# SCH_URC-VPN-New-Project_2025-07-22_1.net
KiCad netlist of a schematic drawn in EasyEDA
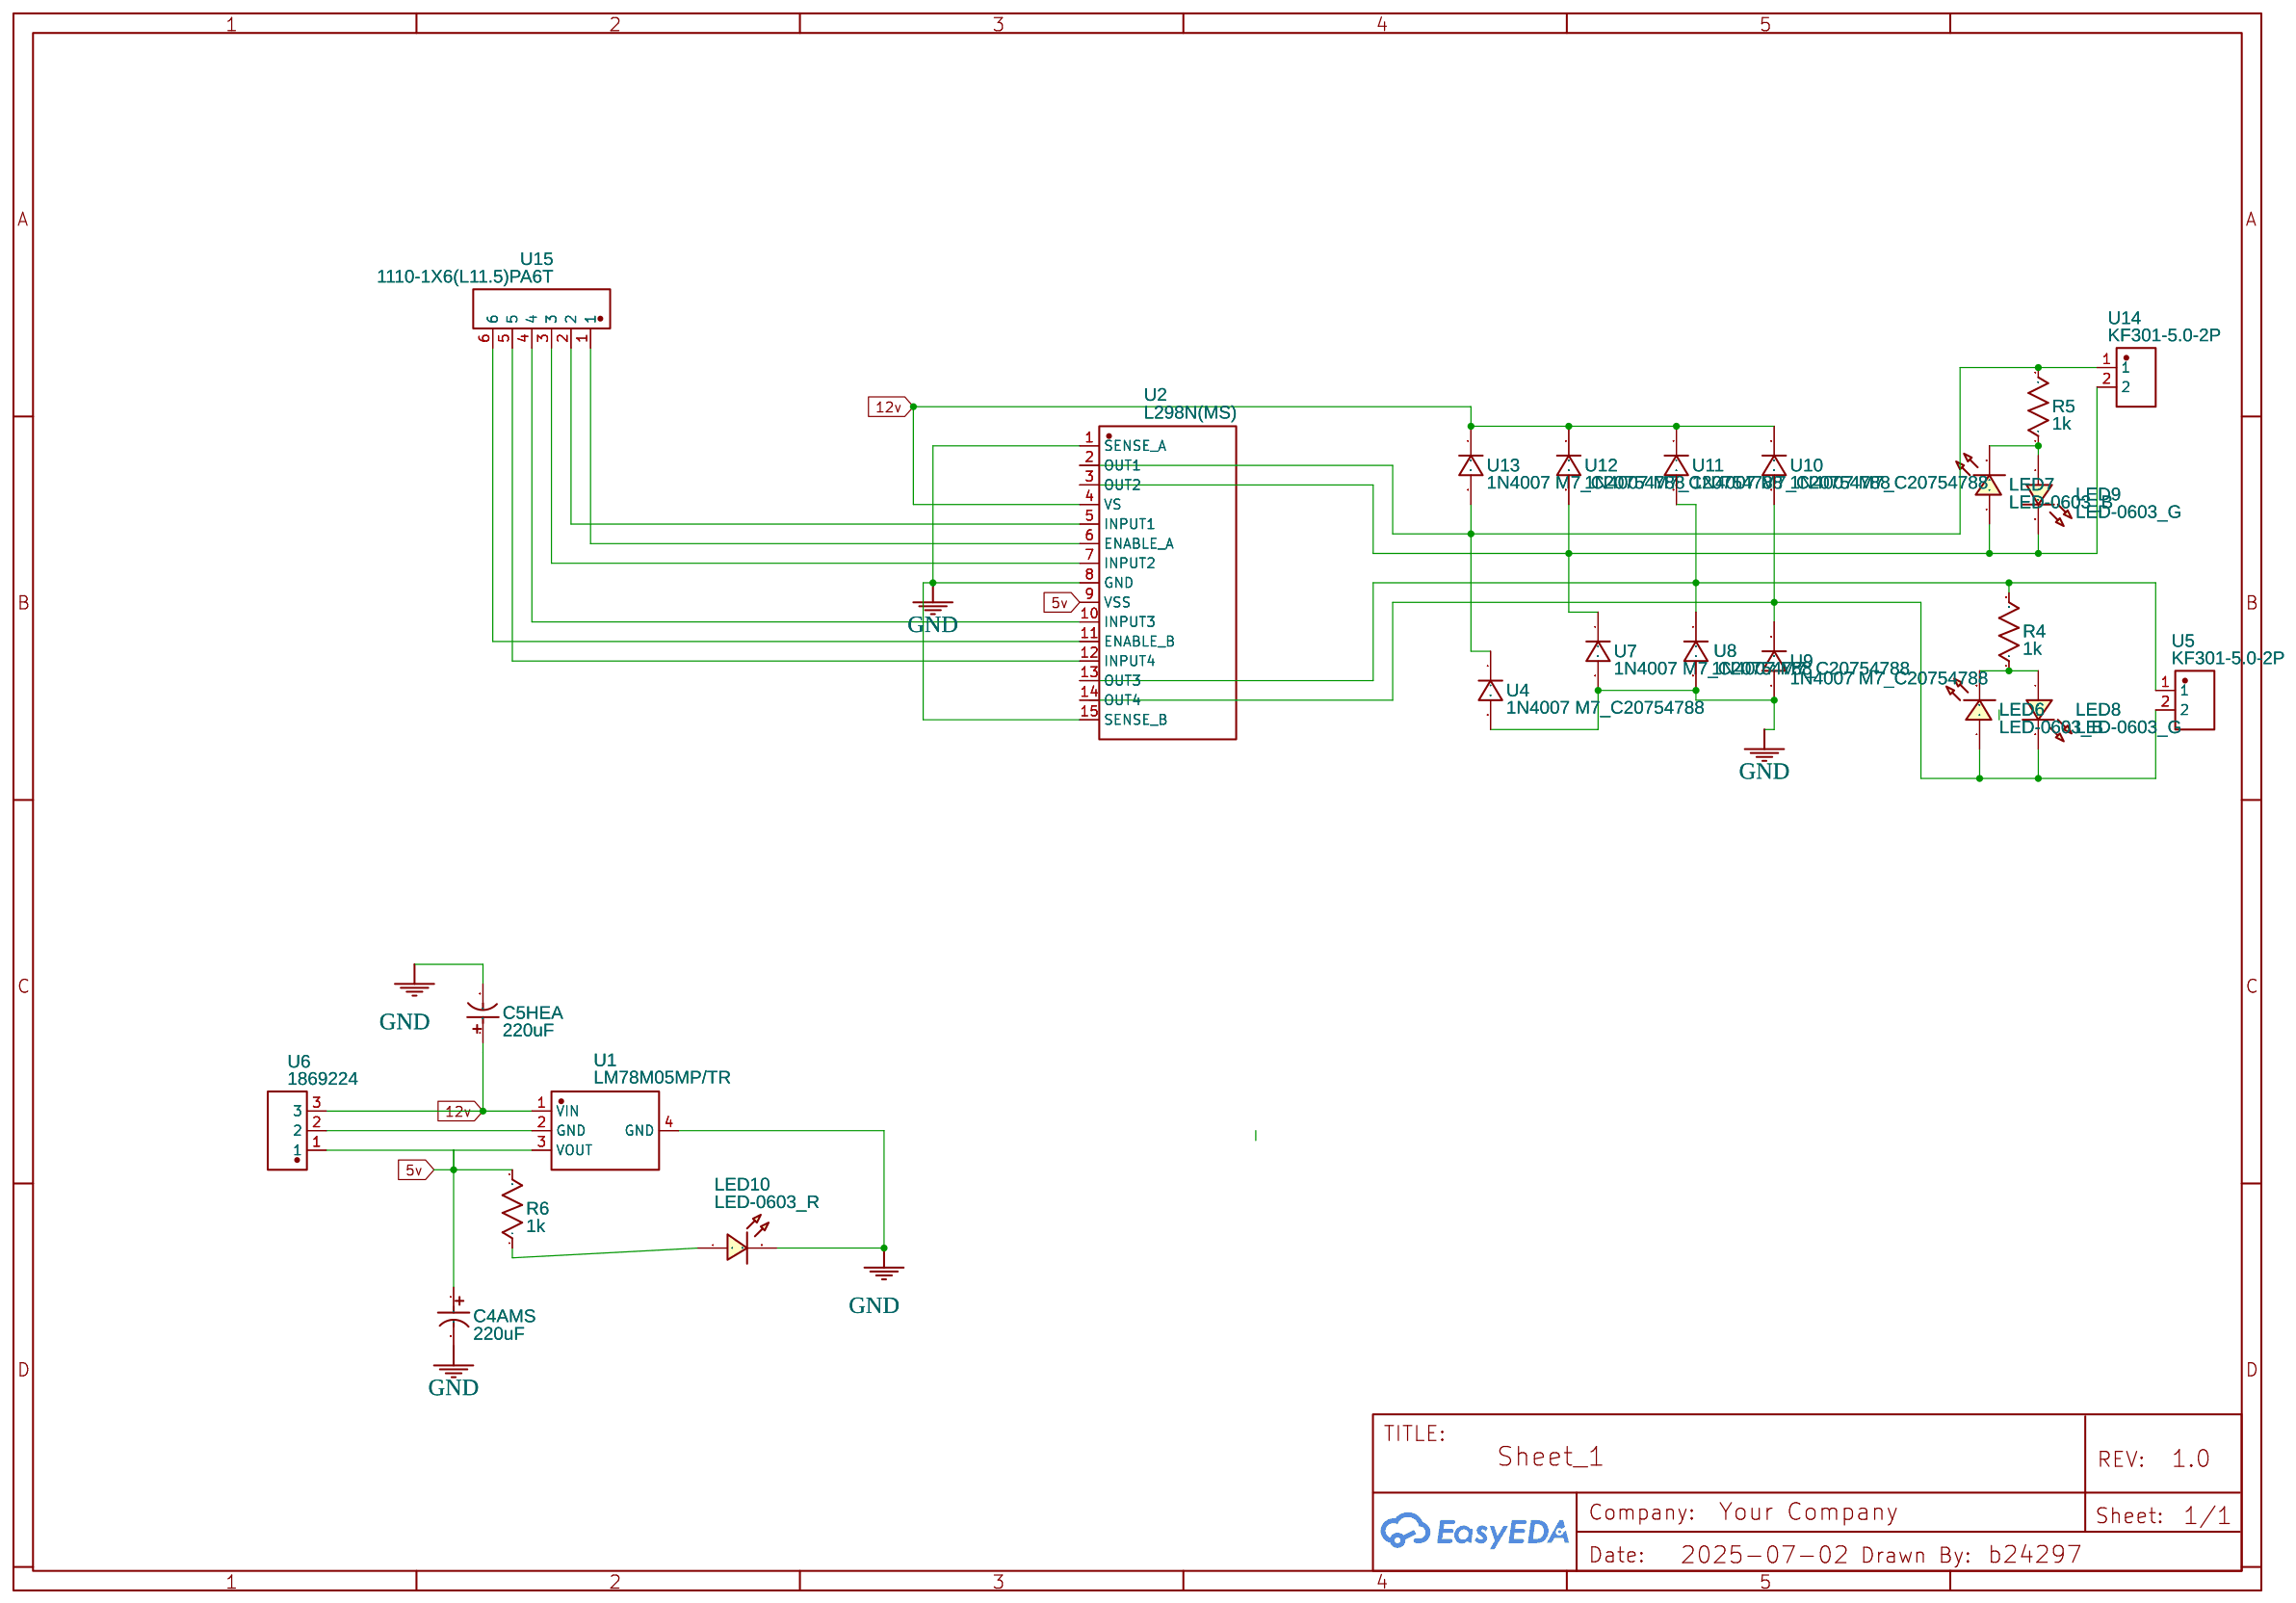
[diagram p0: schematic sheet]

(export (version "E")
  (design (tool "Eeschema 10.0.6"))
  (components
    (comp (ref "C4AMS")
      (value "220uF")
      (fields
        (field (name "Manufacturer Part") "KM227M035F12RR0VH2FP0")
        (field (name "Manufacturer") "CX(承兴)")
      )
      (libsource (lib "") (part "220uf/35V"))
    )
    (comp (ref "C5HEA")
      (value "220uF")
      (fields
        (field (name "Manufacturer Part") "KM227M035F12RR0VH2FP0")
        (field (name "Manufacturer") "CX(承兴)")
      )
      (libsource (lib "") (part "220uf/35V_1"))
    )
    (comp (ref "LED6")
      (value "LED-0603_B")
      (fields
        (field (name "Manufacturer Part") "19-217/BHC-ZL1M2RY/3T")
        (field (name "Manufacturer") "EVERLIGHT(台湾亿光)")
      )
      (libsource (lib "") (part "LED-0603_B"))
    )
    (comp (ref "LED7")
      (value "LED-0603_B")
      (fields
        (field (name "Manufacturer Part") "19-217/BHC-ZL1M2RY/3T")
        (field (name "Manufacturer") "EVERLIGHT(台湾亿光)")
      )
      (libsource (lib "") (part "LED-0603_B"))
    )
    (comp (ref "LED8")
      (value "LED-0603_G")
      (fields
        (field (name "Manufacturer Part") "19-217/GHC-YR1S2/3T")
        (field (name "Manufacturer") "EVERLIGHT(台湾亿光)")
      )
      (libsource (lib "") (part "LED-0603_G"))
    )
    (comp (ref "LED9")
      (value "LED-0603_G")
      (fields
        (field (name "Manufacturer Part") "19-217/GHC-YR1S2/3T")
        (field (name "Manufacturer") "EVERLIGHT(台湾亿光)")
      )
      (libsource (lib "") (part "LED-0603_G"))
    )
    (comp (ref "LED10")
      (value "LED-0603_R")
      (fields
        (field (name "Manufacturer Part") "19-217/R6C-AL1M2VY/3T")
        (field (name "Manufacturer") "EVERLIGHT(台湾亿光)")
      )
      (libsource (lib "") (part "LED-0603_R"))
    )
    (comp (ref "R4") (value "1k") (libsource (lib "") (part "R_0603_US")))
    (comp (ref "R5") (value "1k") (libsource (lib "") (part "R_0603_US")))
    (comp (ref "R6") (value "1k") (libsource (lib "") (part "R_0603_US")))
    (comp (ref "U1")
      (value "LM78M05MP/TR")
      (fields (field (name "Manufacturer") "HGSEMI(华冠)"))
      (libsource (lib "") (part "LM78M05MP/TR"))
    )
    (comp (ref "U2")
      (value "L298N(MS)")
      (fields (field (name "Manufacturer") "MSKSEMI(美森科)"))
      (libsource (lib "") (part "L298N(MS)"))
    )
    (comp (ref "U4")
      (value "1N4007 M7_C20754788")
      (fields (field (name "Manufacturer Part") "1N4007 M7") (field (name "Manufacturer") "JSMSEMI(杰盛微)"))
      (libsource (lib "") (part "1N4007 M7_C20754788"))
    )
    (comp (ref "U5")
      (value "KF301-5.0-2P")
      (fields (field (name "Manufacturer") "KEFA(科发)"))
      (libsource (lib "") (part "KF301-5.0-2P"))
    )
    (comp (ref "U6")
      (value "1869224")
      (fields (field (name "Manufacturer") "Phoenix Contact(菲尼克斯)"))
      (libsource (lib "") (part "1869224"))
    )
    (comp (ref "U7")
      (value "1N4007 M7_C20754788")
      (fields (field (name "Manufacturer Part") "1N4007 M7") (field (name "Manufacturer") "JSMSEMI(杰盛微)"))
      (libsource (lib "") (part "1N4007 M7_C20754788"))
    )
    (comp (ref "U8")
      (value "1N4007 M7_C20754788")
      (fields (field (name "Manufacturer Part") "1N4007 M7") (field (name "Manufacturer") "JSMSEMI(杰盛微)"))
      (libsource (lib "") (part "1N4007 M7_C20754788"))
    )
    (comp (ref "U9")
      (value "1N4007 M7_C20754788")
      (fields (field (name "Manufacturer Part") "1N4007 M7") (field (name "Manufacturer") "JSMSEMI(杰盛微)"))
      (libsource (lib "") (part "1N4007 M7_C20754788"))
    )
    (comp (ref "U10")
      (value "1N4007 M7_C20754788")
      (fields (field (name "Manufacturer Part") "1N4007 M7") (field (name "Manufacturer") "JSMSEMI(杰盛微)"))
      (libsource (lib "") (part "1N4007 M7_C20754788"))
    )
    (comp (ref "U11")
      (value "1N4007 M7_C20754788")
      (fields (field (name "Manufacturer Part") "1N4007 M7") (field (name "Manufacturer") "JSMSEMI(杰盛微)"))
      (libsource (lib "") (part "1N4007 M7_C20754788"))
    )
    (comp (ref "U12")
      (value "1N4007 M7_C20754788")
      (fields (field (name "Manufacturer Part") "1N4007 M7") (field (name "Manufacturer") "JSMSEMI(杰盛微)"))
      (libsource (lib "") (part "1N4007 M7_C20754788"))
    )
    (comp (ref "U13")
      (value "1N4007 M7_C20754788")
      (fields (field (name "Manufacturer Part") "1N4007 M7") (field (name "Manufacturer") "JSMSEMI(杰盛微)"))
      (libsource (lib "") (part "1N4007 M7_C20754788"))
    )
    (comp (ref "U14")
      (value "KF301-5.0-2P")
      (fields (field (name "Manufacturer") "KEFA(科发)"))
      (libsource (lib "") (part "KF301-5.0-2P"))
    )
    (comp (ref "U15")
      (value "1110-1X6(L11.5)PA6T")
      (fields
        (field (name "Manufacturer Part") "1110-1x6(L11.5)PA6T")
        (field (name "Manufacturer") "CST(永丰盈)")
      )
      (libsource (lib "") (part "1110-1X6(L11.5)PA6T"))
    )
  )
  (nets
    (net (code "1") (name "5v") (class "Default")
      (node (ref "C4AMS") (pin "1") (pinfunction "1_1") (pintype "input"))
      (node (ref "R6") (pin "2") (pinfunction "2_2") (pintype "unspecified"))
      (node (ref "U1") (pin "3") (pinfunction "VOUT_3") (pintype "unspecified"))
      (node (ref "U2") (pin "9") (pinfunction "VSS_9") (pintype "unspecified"))
      (node (ref "U6") (pin "1") (pinfunction "1_1") (pintype "unspecified"))
    )
    (net (code "2") (name "12v") (class "Default")
      (node (ref "C5HEA") (pin "1") (pinfunction "1_1") (pintype "input"))
      (node (ref "U1") (pin "1") (pinfunction "VIN_1") (pintype "unspecified"))
      (node (ref "U10") (pin "1") (pinfunction "1_1") (pintype "unspecified"))
      (node (ref "U11") (pin "1") (pinfunction "1_1") (pintype "unspecified"))
      (node (ref "U12") (pin "1") (pinfunction "1_1") (pintype "unspecified"))
      (node (ref "U13") (pin "1") (pinfunction "1_1") (pintype "unspecified"))
      (node (ref "U2") (pin "4") (pinfunction "VS_4") (pintype "unspecified"))
      (node (ref "U6") (pin "3") (pinfunction "3_3") (pintype "unspecified"))
    )
    (net (code "3") (name "GND") (class "Default")
      (node (ref "C4AMS") (pin "2") (pinfunction "2_2") (pintype "input"))
      (node (ref "C5HEA") (pin "2") (pinfunction "2_2") (pintype "input"))
      (node (ref "LED10") (pin "2") (pinfunction "2_2") (pintype "unspecified"))
      (node (ref "U1") (pin "4") (pinfunction "GND_4") (pintype "unspecified"))
      (node (ref "U2") (pin "1") (pinfunction "SENSE_A_1") (pintype "unspecified"))
      (node (ref "U2") (pin "15") (pinfunction "SENSE_B_15") (pintype "unspecified"))
      (node (ref "U2") (pin "8") (pinfunction "GND_8") (pintype "unspecified"))
      (node (ref "U4") (pin "2") (pinfunction "2_2") (pintype "unspecified"))
      (node (ref "U7") (pin "2") (pinfunction "2_2") (pintype "unspecified"))
      (node (ref "U8") (pin "2") (pinfunction "2_2") (pintype "unspecified"))
      (node (ref "U9") (pin "2") (pinfunction "2_2") (pintype "unspecified"))
    )
    (net (code "4") (name "Net-(LED6-Pad1)") (class "Default")
      (node (ref "LED6") (pin "1") (pinfunction "1_1") (pintype "unspecified"))
      (node (ref "LED8") (pin "2") (pinfunction "2_2") (pintype "unspecified"))
      (node (ref "U10") (pin "2") (pinfunction "2_2") (pintype "unspecified"))
      (node (ref "U5") (pin "2") (pinfunction "2_2") (pintype "unspecified"))
      (node (ref "U9") (pin "1") (pinfunction "1_1") (pintype "unspecified"))
    )
    (net (code "5") (name "Net-(LED6-Pad2)") (class "Default")
      (node (ref "LED6") (pin "2") (pinfunction "2_2") (pintype "unspecified"))
      (node (ref "LED8") (pin "1") (pinfunction "1_1") (pintype "unspecified"))
      (node (ref "R4") (pin "1") (pinfunction "1_1") (pintype "unspecified"))
    )
    (net (code "6") (name "Net-(LED7-Pad2)") (class "Default")
      (node (ref "LED7") (pin "2") (pinfunction "2_2") (pintype "unspecified"))
      (node (ref "LED9") (pin "1") (pinfunction "1_1") (pintype "unspecified"))
      (node (ref "R5") (pin "1") (pinfunction "1_1") (pintype "unspecified"))
    )
    (net (code "7") (name "Net-(LED10-Pad1)") (class "Default")
      (node (ref "LED10") (pin "1") (pinfunction "1_1") (pintype "unspecified"))
      (node (ref "R6") (pin "1") (pinfunction "1_1") (pintype "unspecified"))
    )
    (net (code "8") (name "Net-(U1-GND-Pad2)") (class "Default")
      (node (ref "U1") (pin "2") (pinfunction "GND_2") (pintype "unspecified"))
      (node (ref "U6") (pin "2") (pinfunction "2_2") (pintype "unspecified"))
    )
    (net (code "9") (name "Net-(U2-ENABLE_A)") (class "Default")
      (node (ref "U15") (pin "1") (pinfunction "1_1") (pintype "unspecified"))
      (node (ref "U2") (pin "6") (pinfunction "ENABLE_A_6") (pintype "unspecified"))
    )
    (net (code "10") (name "Net-(U2-ENABLE_B)") (class "Default")
      (node (ref "U15") (pin "6") (pinfunction "6_6") (pintype "unspecified"))
      (node (ref "U2") (pin "11") (pinfunction "ENABLE_B_11") (pintype "unspecified"))
    )
    (net (code "11") (name "Net-(U2-INPUT1)") (class "Default")
      (node (ref "U15") (pin "2") (pinfunction "2_2") (pintype "unspecified"))
      (node (ref "U2") (pin "5") (pinfunction "INPUT1_5") (pintype "unspecified"))
    )
    (net (code "12") (name "Net-(U2-INPUT2)") (class "Default")
      (node (ref "U15") (pin "3") (pinfunction "3_3") (pintype "unspecified"))
      (node (ref "U2") (pin "7") (pinfunction "INPUT2_7") (pintype "unspecified"))
    )
    (net (code "13") (name "Net-(U2-INPUT3)") (class "Default")
      (node (ref "U15") (pin "4") (pinfunction "4_4") (pintype "unspecified"))
      (node (ref "U2") (pin "10") (pinfunction "INPUT3_10") (pintype "unspecified"))
    )
    (net (code "14") (name "Net-(U2-INPUT4)") (class "Default")
      (node (ref "U15") (pin "5") (pinfunction "5_5") (pintype "unspecified"))
      (node (ref "U2") (pin "12") (pinfunction "INPUT4_12") (pintype "unspecified"))
    )
    (net (code "15") (name "Net-(U2-OUT1)") (class "Default")
      (node (ref "R5") (pin "2") (pinfunction "2_2") (pintype "unspecified"))
      (node (ref "U13") (pin "2") (pinfunction "2_2") (pintype "unspecified"))
      (node (ref "U14") (pin "1") (pinfunction "1_1") (pintype "unspecified"))
      (node (ref "U2") (pin "2") (pinfunction "OUT1_2") (pintype "unspecified"))
      (node (ref "U4") (pin "1") (pinfunction "1_1") (pintype "unspecified"))
    )
    (net (code "16") (name "Net-(U2-OUT2)") (class "Default")
      (node (ref "LED7") (pin "1") (pinfunction "1_1") (pintype "unspecified"))
      (node (ref "LED9") (pin "2") (pinfunction "2_2") (pintype "unspecified"))
      (node (ref "U12") (pin "2") (pinfunction "2_2") (pintype "unspecified"))
      (node (ref "U14") (pin "2") (pinfunction "2_2") (pintype "unspecified"))
      (node (ref "U2") (pin "3") (pinfunction "OUT2_3") (pintype "unspecified"))
      (node (ref "U7") (pin "1") (pinfunction "1_1") (pintype "unspecified"))
    )
    (net (code "17") (name "Net-(U2-OUT3)") (class "Default")
      (node (ref "R4") (pin "2") (pinfunction "2_2") (pintype "unspecified"))
      (node (ref "U11") (pin "2") (pinfunction "2_2") (pintype "unspecified"))
      (node (ref "U2") (pin "13") (pinfunction "OUT3_13") (pintype "unspecified"))
      (node (ref "U5") (pin "1") (pinfunction "1_1") (pintype "unspecified"))
      (node (ref "U8") (pin "1") (pinfunction "1_1") (pintype "unspecified"))
    )
    (net (code "18") (name "unconnected-(U2-OUT4-Pad14)") (class "Default")
      (node (ref "U2") (pin "14") (pinfunction "OUT4_14") (pintype "unspecified"))
    )
  )
)
